# 1-Schematic_STM32_CC1101_USBMALE_PCBANTE.net
KiCad netlist of a schematic drawn in EasyEDA
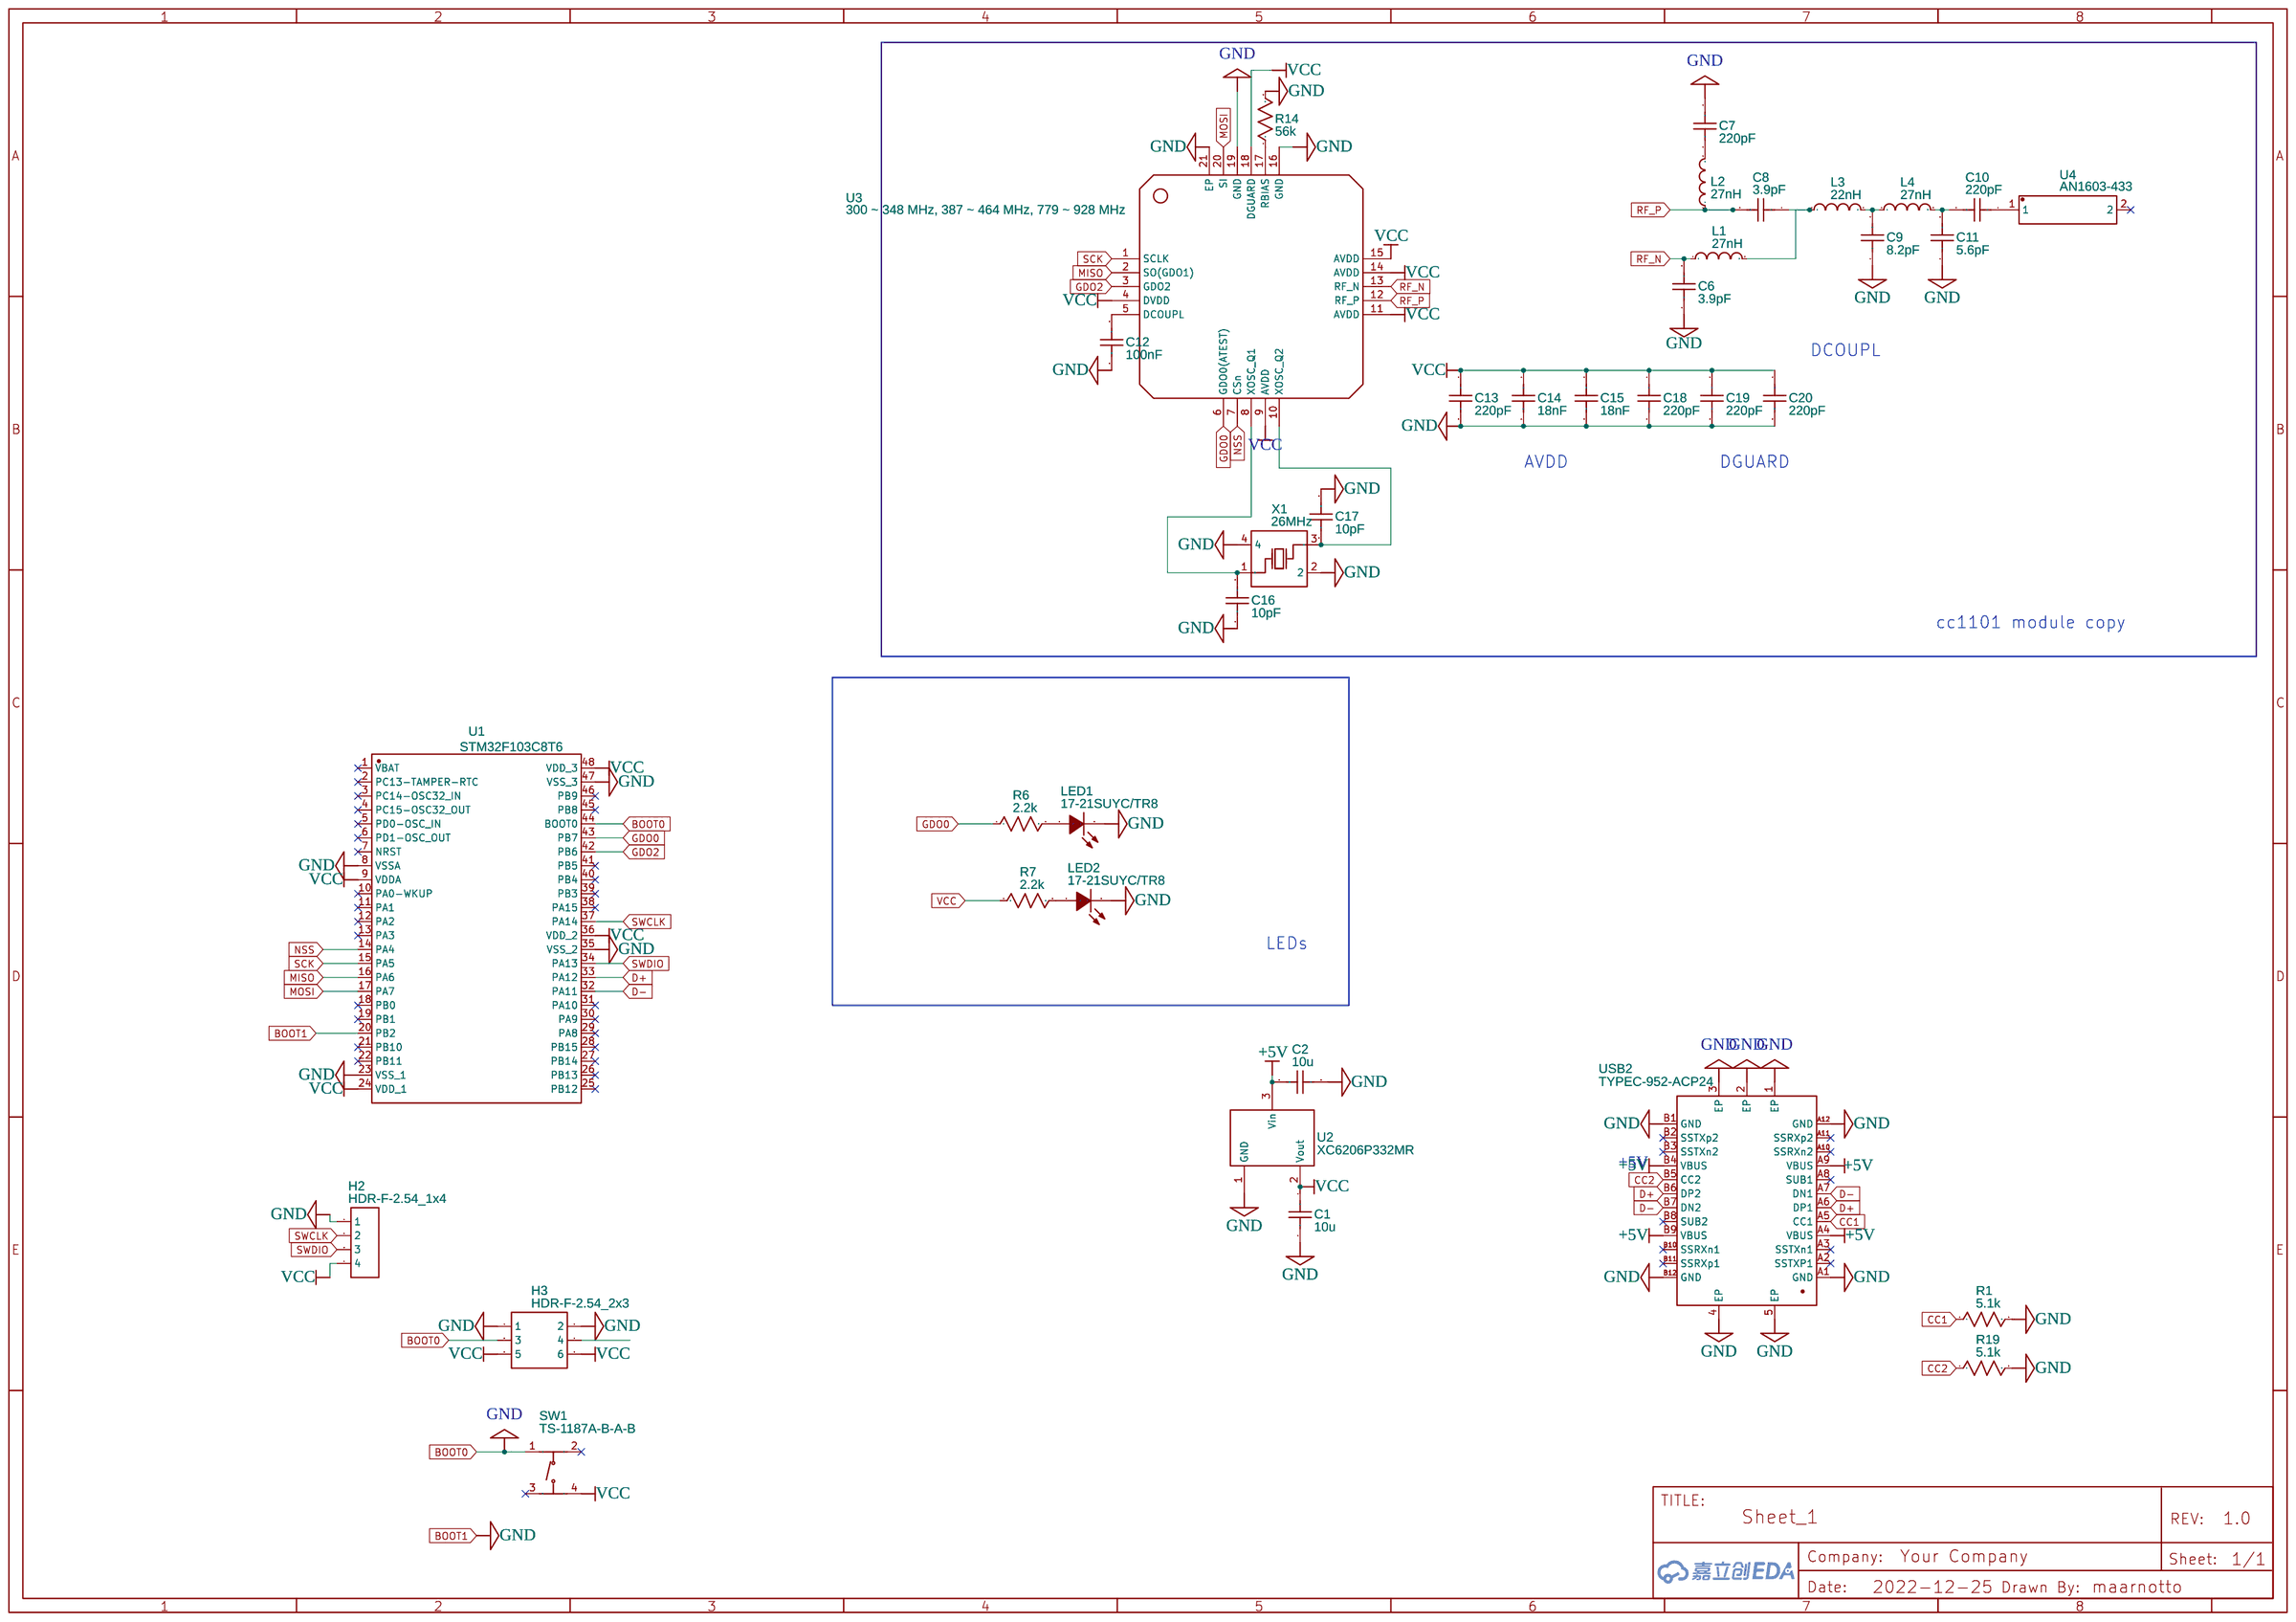
[diagram p0: schematic sheet]

(export (version "E")
  (design (tool "Eeschema 10.0.6"))
  (components
    (comp (ref "C1") (value "10u") (libsource (lib "") (part "C_0603_US_1")))
    (comp (ref "C2") (value "10u") (libsource (lib "") (part "C_0603_US")))
    (comp (ref "C6") (value "3.9pF") (libsource (lib "") (part "C_0402_US_2")))
    (comp (ref "C7") (value "220pF") (libsource (lib "") (part "C_0402_US_2")))
    (comp (ref "C8") (value "3.9pF") (libsource (lib "") (part "C_0402_US")))
    (comp (ref "C9") (value "8.2pF") (libsource (lib "") (part "C_0402_US_2")))
    (comp (ref "C10") (value "220pF") (libsource (lib "") (part "C_0402_US")))
    (comp (ref "C11") (value "5.6pF") (libsource (lib "") (part "C_0402_US_2")))
    (comp (ref "C12") (value "100nF") (libsource (lib "") (part "C_0402_US_1")))
    (comp (ref "C13") (value "220pF") (libsource (lib "") (part "C_0402_US_1")))
    (comp (ref "C14") (value "18nF") (libsource (lib "") (part "C_0402_US_1")))
    (comp (ref "C15") (value "18nF") (libsource (lib "") (part "C_0402_US_1")))
    (comp (ref "C16") (value "10pF") (libsource (lib "") (part "C_0402_US_1")))
    (comp (ref "C17") (value "10pF") (libsource (lib "") (part "C_0402_US_2")))
    (comp (ref "C18") (value "220pF") (libsource (lib "") (part "C_0402_US_1")))
    (comp (ref "C19") (value "220pF") (libsource (lib "") (part "C_0402_US_1")))
    (comp (ref "C20") (value "220pF") (libsource (lib "") (part "C_0402_US_1")))
    (comp (ref "H2")
      (value "HDR-F-2.54_1x4")
      (fields (field (name "BOM_Supplier Part") "C225501"))
      (libsource (lib "") (part "HDR-F-2.54_1x4"))
    )
    (comp (ref "H3")
      (value "HDR-F-2.54_2x3")
      (fields (field (name "BOM_Supplier Part") "C65114"))
      (libsource (lib "") (part "HDR-F-2.54_2x3"))
    )
    (comp (ref "L1") (value "27nH") (libsource (lib "") (part "L0402_US")))
    (comp (ref "L2") (value "27nH") (libsource (lib "") (part "L0402_US_1")))
    (comp (ref "L3") (value "22nH") (libsource (lib "") (part "L0402_US")))
    (comp (ref "L4") (value "27nH") (libsource (lib "") (part "L0402_US")))
    (comp (ref "LED1")
      (value "17-21SUYC/TR8")
      (fields
        (field (name "BOM_Manufacturer Part") "KT-0805黄灯 (SMT业务专用)")
        (field (name "BOM_Supplier Part") "C2296")
      )
      (libsource (lib "") (part "17-21SUYC/TR8"))
    )
    (comp (ref "LED2")
      (value "17-21SUYC/TR8")
      (fields
        (field (name "BOM_Manufacturer Part") "KT-0805黄灯 (SMT业务专用)")
        (field (name "BOM_Supplier Part") "C2296")
      )
      (libsource (lib "") (part "17-21SUYC/TR8"))
    )
    (comp (ref "R1") (value "5.1k") (libsource (lib "") (part "R_0603_US")))
    (comp (ref "R6") (value "2.2k") (libsource (lib "") (part "R_0603_US")))
    (comp (ref "R7") (value "2.2k") (libsource (lib "") (part "R_0603_US")))
    (comp (ref "R14") (value "56k") (libsource (lib "") (part "R_0402_US")))
    (comp (ref "R19") (value "5.1k") (libsource (lib "") (part "R_0603_US")))
    (comp (ref "SW1")
      (value "TS-1187A-B-A-B")
      (fields (field (name "BOM_Supplier Part") "C318884"))
      (libsource (lib "") (part "TS-1187A-B-A-B"))
    )
    (comp (ref "U1")
      (value "STM32F103C8T6")
      (fields (field (name "BOM_Supplier Part") "C8734"))
      (libsource (lib "") (part "STM32F103C8T6"))
    )
    (comp (ref "U2")
      (value "XC6206P332MR")
      (fields (field (name "BOM_Supplier Part") "C5446"))
      (libsource (lib "") (part "XC6206P332MR"))
    )
    (comp (ref "U3")
      (value "300 ~ 348 MHz, 387 ~ 464 MHz, 779 ~ 928 MHz")
      (fields (field (name "BOM_Manufacturer Part") "CC1101RGPR") (field (name "BOM_Supplier Part") "C29953"))
      (libsource (lib "") (part "CC1101RGPR"))
    )
    (comp (ref "U4")
      (value "AN1603-433")
      (fields (field (name "BOM_Supplier Part") "C122806"))
      (libsource (lib "") (part "AN1603-433"))
    )
    (comp (ref "USB2")
      (value "TYPEC-952-ACP24")
      (fields (field (name "BOM_Supplier Part") "C2840398"))
      (libsource (lib "") (part "TYPEC-952-ACP24"))
    )
    (comp (ref "X1")
      (value "26MHz")
      (fields
        (field (name "BOM_Manufacturer Part") "3S26000333")
        (field (name "BOM_Supplier Part") "C431163")
      )
      (libsource (lib "") (part "3S26000333"))
    )
  )
  (nets
    (net (code "1") (name "+5V") (class "Default")
      (node (ref "C2") (pin "2") (pinfunction "2_2") (pintype "unspecified"))
      (node (ref "U2") (pin "3") (pinfunction "Vin_3") (pintype "unspecified"))
      (node (ref "USB2") (pin "A4") (pinfunction "VBUS_A4") (pintype "unspecified"))
      (node (ref "USB2") (pin "A9") (pinfunction "VBUS_A9") (pintype "unspecified"))
      (node (ref "USB2") (pin "B4") (pinfunction "VBUS_B4") (pintype "unspecified"))
      (node (ref "USB2") (pin "B9") (pinfunction "VBUS_B9") (pintype "unspecified"))
    )
    (net (code "2") (name "BOOT0") (class "Default")
      (node (ref "C1") (pin "2") (pinfunction "2_2") (pintype "unspecified"))
      (node (ref "C11") (pin "1") (pinfunction "1_1") (pintype "unspecified"))
      (node (ref "C12") (pin "2") (pinfunction "2_2") (pintype "unspecified"))
      (node (ref "C13") (pin "2") (pinfunction "2_2") (pintype "unspecified"))
      (node (ref "C14") (pin "2") (pinfunction "2_2") (pintype "unspecified"))
      (node (ref "C15") (pin "2") (pinfunction "2_2") (pintype "unspecified"))
      (node (ref "C16") (pin "2") (pinfunction "2_2") (pintype "unspecified"))
      (node (ref "C17") (pin "2") (pinfunction "2_2") (pintype "unspecified"))
      (node (ref "C18") (pin "2") (pinfunction "2_2") (pintype "unspecified"))
      (node (ref "C19") (pin "2") (pinfunction "2_2") (pintype "unspecified"))
      (node (ref "C2") (pin "1") (pinfunction "1_1") (pintype "unspecified"))
      (node (ref "C20") (pin "2") (pinfunction "2_2") (pintype "unspecified"))
      (node (ref "C6") (pin "1") (pinfunction "1_1") (pintype "unspecified"))
      (node (ref "C7") (pin "2") (pinfunction "2_2") (pintype "unspecified"))
      (node (ref "C9") (pin "1") (pinfunction "1_1") (pintype "unspecified"))
      (node (ref "H2") (pin "1") (pinfunction "1_1") (pintype "unspecified"))
      (node (ref "H3") (pin "1") (pinfunction "1_1") (pintype "input"))
      (node (ref "H3") (pin "2") (pinfunction "2_2") (pintype "input"))
      (node (ref "H3") (pin "3") (pinfunction "3_3") (pintype "input"))
      (node (ref "LED1") (pin "2") (pinfunction "-_2") (pintype "unspecified"))
      (node (ref "LED2") (pin "2") (pinfunction "-_2") (pintype "unspecified"))
      (node (ref "R1") (pin "2") (pinfunction "2_2") (pintype "unspecified"))
      (node (ref "R14") (pin "2") (pinfunction "2_2") (pintype "unspecified"))
      (node (ref "R19") (pin "2") (pinfunction "2_2") (pintype "unspecified"))
      (node (ref "SW1") (pin "1") (pinfunction "A_1") (pintype "unspecified"))
      (node (ref "U1") (pin "20") (pinfunction "PB2_20") (pintype "unspecified"))
      (node (ref "U1") (pin "23") (pinfunction "VSS_1_23") (pintype "unspecified"))
      (node (ref "U1") (pin "35") (pinfunction "VSS_2_35") (pintype "unspecified"))
      (node (ref "U1") (pin "44") (pinfunction "BOOT0_44") (pintype "unspecified"))
      (node (ref "U1") (pin "47") (pinfunction "VSS_3_47") (pintype "unspecified"))
      (node (ref "U1") (pin "8") (pinfunction "VSSA_8") (pintype "unspecified"))
      (node (ref "U2") (pin "1") (pinfunction "GND_1") (pintype "unspecified"))
      (node (ref "U3") (pin "16") (pinfunction "GND_16") (pintype "unspecified"))
      (node (ref "U3") (pin "19") (pinfunction "GND_19") (pintype "unspecified"))
      (node (ref "U3") (pin "21") (pinfunction "EP_21") (pintype "unspecified"))
      (node (ref "USB2") (pin "1") (pinfunction "EP_1") (pintype "unspecified"))
      (node (ref "USB2") (pin "2") (pinfunction "EP_2") (pintype "unspecified"))
      (node (ref "USB2") (pin "3") (pinfunction "EP_3") (pintype "unspecified"))
      (node (ref "USB2") (pin "4") (pinfunction "EP_4") (pintype "unspecified"))
      (node (ref "USB2") (pin "5") (pinfunction "EP_5") (pintype "unspecified"))
      (node (ref "USB2") (pin "A1") (pinfunction "GND_A1") (pintype "unspecified"))
      (node (ref "USB2") (pin "A12") (pinfunction "GND_A12") (pintype "unspecified"))
      (node (ref "USB2") (pin "B1") (pinfunction "GND_B1") (pintype "unspecified"))
      (node (ref "USB2") (pin "B12") (pinfunction "GND_B12") (pintype "unspecified"))
      (node (ref "X1") (pin "2") (pinfunction "2_2") (pintype "unspecified"))
      (node (ref "X1") (pin "4") (pinfunction "4_4") (pintype "unspecified"))
    )
    (net (code "3") (name "CC1") (class "Default")
      (node (ref "R1") (pin "1") (pinfunction "1_1") (pintype "unspecified"))
      (node (ref "USB2") (pin "A5") (pinfunction "CC1_A5") (pintype "unspecified"))
    )
    (net (code "4") (name "CC2") (class "Default")
      (node (ref "R19") (pin "1") (pinfunction "1_1") (pintype "unspecified"))
      (node (ref "USB2") (pin "B5") (pinfunction "CC2_B5") (pintype "unspecified"))
    )
    (net (code "5") (name "D+") (class "Default")
      (node (ref "U1") (pin "33") (pinfunction "PA12_33") (pintype "unspecified"))
      (node (ref "USB2") (pin "A6") (pinfunction "DP1_A6") (pintype "unspecified"))
      (node (ref "USB2") (pin "B6") (pinfunction "DP2_B6") (pintype "unspecified"))
    )
    (net (code "6") (name "D-") (class "Default")
      (node (ref "U1") (pin "32") (pinfunction "PA11_32") (pintype "unspecified"))
      (node (ref "USB2") (pin "A7") (pinfunction "DN1_A7") (pintype "unspecified"))
      (node (ref "USB2") (pin "B7") (pinfunction "DN2_B7") (pintype "unspecified"))
    )
    (net (code "7") (name "GDO0") (class "Default")
      (node (ref "R6") (pin "1") (pinfunction "1_1") (pintype "unspecified"))
      (node (ref "U1") (pin "43") (pinfunction "PB7_43") (pintype "unspecified"))
      (node (ref "U3") (pin "6") (pinfunction "GDO0(ATEST)_6") (pintype "unspecified"))
    )
    (net (code "8") (name "GDO2") (class "Default")
      (node (ref "U1") (pin "42") (pinfunction "PB6_42") (pintype "unspecified"))
      (node (ref "U3") (pin "3") (pinfunction "GDO2_3") (pintype "unspecified"))
    )
    (net (code "9") (name "MISO") (class "Default")
      (node (ref "U1") (pin "16") (pinfunction "PA6_16") (pintype "unspecified"))
      (node (ref "U3") (pin "2") (pinfunction "SO(GDO1)_2") (pintype "unspecified"))
    )
    (net (code "10") (name "MOSI") (class "Default")
      (node (ref "U1") (pin "17") (pinfunction "PA7_17") (pintype "unspecified"))
      (node (ref "U3") (pin "20") (pinfunction "SI_20") (pintype "unspecified"))
    )
    (net (code "11") (name "NSS") (class "Default")
      (node (ref "U1") (pin "14") (pinfunction "PA4_14") (pintype "unspecified"))
      (node (ref "U3") (pin "7") (pinfunction "CSn_7") (pintype "unspecified"))
    )
    (net (code "12") (name "Net-(C7-Pad1)") (class "Default")
      (node (ref "C7") (pin "1") (pinfunction "1_1") (pintype "unspecified"))
      (node (ref "L2") (pin "2") (pinfunction "2_2") (pintype "unspecified"))
    )
    (net (code "13") (name "Net-(C8-Pad1)") (class "Default")
      (node (ref "C8") (pin "1") (pinfunction "1_1") (pintype "unspecified"))
      (node (ref "L1") (pin "2") (pinfunction "2_2") (pintype "unspecified"))
      (node (ref "L3") (pin "1") (pinfunction "1_1") (pintype "unspecified"))
    )
    (net (code "14") (name "Net-(C9-Pad2)") (class "Default")
      (node (ref "C9") (pin "2") (pinfunction "2_2") (pintype "unspecified"))
      (node (ref "L3") (pin "2") (pinfunction "2_2") (pintype "unspecified"))
      (node (ref "L4") (pin "1") (pinfunction "1_1") (pintype "unspecified"))
    )
    (net (code "15") (name "Net-(C10-Pad1)") (class "Default")
      (node (ref "C10") (pin "1") (pinfunction "1_1") (pintype "unspecified"))
      (node (ref "U4") (pin "1") (pinfunction "1_1") (pintype "unspecified"))
    )
    (net (code "16") (name "Net-(C10-Pad2)") (class "Default")
      (node (ref "C10") (pin "2") (pinfunction "2_2") (pintype "unspecified"))
      (node (ref "C11") (pin "2") (pinfunction "2_2") (pintype "unspecified"))
      (node (ref "L4") (pin "2") (pinfunction "2_2") (pintype "unspecified"))
    )
    (net (code "17") (name "Net-(LED1-+)") (class "Default")
      (node (ref "LED1") (pin "1") (pinfunction "+_1") (pintype "unspecified"))
      (node (ref "R6") (pin "2") (pinfunction "2_2") (pintype "unspecified"))
    )
    (net (code "18") (name "Net-(LED2-+)") (class "Default")
      (node (ref "LED2") (pin "1") (pinfunction "+_1") (pintype "unspecified"))
      (node (ref "R7") (pin "2") (pinfunction "2_2") (pintype "unspecified"))
    )
    (net (code "19") (name "Net-(U3-DCOUPL)") (class "Default")
      (node (ref "C12") (pin "1") (pinfunction "1_1") (pintype "unspecified"))
      (node (ref "U3") (pin "5") (pinfunction "DCOUPL_5") (pintype "unspecified"))
    )
    (net (code "20") (name "Net-(U3-RBIAS)") (class "Default")
      (node (ref "R14") (pin "1") (pinfunction "1_1") (pintype "unspecified"))
      (node (ref "U3") (pin "17") (pinfunction "RBIAS_17") (pintype "unspecified"))
    )
    (net (code "21") (name "Net-(U3-XOSC_Q1)") (class "Default")
      (node (ref "C16") (pin "1") (pinfunction "1_1") (pintype "unspecified"))
      (node (ref "U3") (pin "8") (pinfunction "XOSC_Q1_8") (pintype "unspecified"))
      (node (ref "X1") (pin "1") (pinfunction "OSC1_1") (pintype "unspecified"))
    )
    (net (code "22") (name "Net-(U3-XOSC_Q2)") (class "Default")
      (node (ref "C17") (pin "1") (pinfunction "1_1") (pintype "unspecified"))
      (node (ref "U3") (pin "10") (pinfunction "XOSC_Q2_10") (pintype "unspecified"))
      (node (ref "X1") (pin "3") (pinfunction "OSC2_3") (pintype "unspecified"))
    )
    (net (code "23") (name "RF_N") (class "Default")
      (node (ref "C6") (pin "2") (pinfunction "2_2") (pintype "unspecified"))
      (node (ref "L1") (pin "1") (pinfunction "1_1") (pintype "unspecified"))
      (node (ref "U3") (pin "13") (pinfunction "RF_N_13") (pintype "unspecified"))
    )
    (net (code "24") (name "RF_P") (class "Default")
      (node (ref "C8") (pin "2") (pinfunction "2_2") (pintype "unspecified"))
      (node (ref "L2") (pin "1") (pinfunction "1_1") (pintype "unspecified"))
      (node (ref "U3") (pin "12") (pinfunction "RF_P_12") (pintype "unspecified"))
    )
    (net (code "25") (name "SCK") (class "Default")
      (node (ref "U1") (pin "15") (pinfunction "PA5_15") (pintype "unspecified"))
      (node (ref "U3") (pin "1") (pinfunction "SCLK_1") (pintype "unspecified"))
    )
    (net (code "26") (name "SWCLK") (class "Default")
      (node (ref "H2") (pin "2") (pinfunction "2_2") (pintype "unspecified"))
      (node (ref "U1") (pin "37") (pinfunction "PA14_37") (pintype "unspecified"))
    )
    (net (code "27") (name "SWDIO") (class "Default")
      (node (ref "H2") (pin "3") (pinfunction "3_3") (pintype "unspecified"))
      (node (ref "U1") (pin "34") (pinfunction "PA13_34") (pintype "unspecified"))
    )
    (net (code "28") (name "VCC") (class "Default")
      (node (ref "C1") (pin "1") (pinfunction "1_1") (pintype "unspecified"))
      (node (ref "C13") (pin "1") (pinfunction "1_1") (pintype "unspecified"))
      (node (ref "C14") (pin "1") (pinfunction "1_1") (pintype "unspecified"))
      (node (ref "C15") (pin "1") (pinfunction "1_1") (pintype "unspecified"))
      (node (ref "C18") (pin "1") (pinfunction "1_1") (pintype "unspecified"))
      (node (ref "C19") (pin "1") (pinfunction "1_1") (pintype "unspecified"))
      (node (ref "C20") (pin "1") (pinfunction "1_1") (pintype "unspecified"))
      (node (ref "H2") (pin "4") (pinfunction "4_4") (pintype "unspecified"))
      (node (ref "H3") (pin "5") (pinfunction "5_5") (pintype "input"))
      (node (ref "H3") (pin "6") (pinfunction "6_6") (pintype "input"))
      (node (ref "R7") (pin "1") (pinfunction "1_1") (pintype "unspecified"))
      (node (ref "SW1") (pin "4") (pinfunction "D_4") (pintype "unspecified"))
      (node (ref "U1") (pin "24") (pinfunction "VDD_1_24") (pintype "unspecified"))
      (node (ref "U1") (pin "36") (pinfunction "VDD_2_36") (pintype "unspecified"))
      (node (ref "U1") (pin "48") (pinfunction "VDD_3_48") (pintype "unspecified"))
      (node (ref "U1") (pin "9") (pinfunction "VDDA_9") (pintype "unspecified"))
      (node (ref "U2") (pin "2") (pinfunction "Vout_2") (pintype "unspecified"))
      (node (ref "U3") (pin "11") (pinfunction "AVDD_11") (pintype "unspecified"))
      (node (ref "U3") (pin "14") (pinfunction "AVDD_14") (pintype "unspecified"))
      (node (ref "U3") (pin "15") (pinfunction "AVDD_15") (pintype "unspecified"))
      (node (ref "U3") (pin "18") (pinfunction "DGUARD_18") (pintype "unspecified"))
      (node (ref "U3") (pin "4") (pinfunction "DVDD_4") (pintype "unspecified"))
      (node (ref "U3") (pin "9") (pinfunction "AVDD_9") (pintype "unspecified"))
    )
    (net (code "29") (name "unconnected-(H3-Pad4)") (class "Default")
      (node (ref "H3") (pin "4") (pinfunction "4_4") (pintype "input"))
    )
    (net (code "30") (name "unconnected-(SW1-B-Pad2)") (class "Default")
      (node (ref "SW1") (pin "2") (pinfunction "B_2") (pintype "unspecified+no_connect"))
    )
    (net (code "31") (name "unconnected-(SW1-C-Pad3)") (class "Default")
      (node (ref "SW1") (pin "3") (pinfunction "C_3") (pintype "unspecified+no_connect"))
    )
    (net (code "32") (name "unconnected-(U1-NRST-Pad7)") (class "Default")
      (node (ref "U1") (pin "7") (pinfunction "NRST_7") (pintype "unspecified+no_connect"))
    )
    (net (code "33") (name "unconnected-(U1-PA0-WKUP-Pad10)") (class "Default")
      (node (ref "U1") (pin "10") (pinfunction "PA0-WKUP_10") (pintype "unspecified+no_connect"))
    )
    (net (code "34") (name "unconnected-(U1-PA1-Pad11)") (class "Default")
      (node (ref "U1") (pin "11") (pinfunction "PA1_11") (pintype "unspecified+no_connect"))
    )
    (net (code "35") (name "unconnected-(U1-PA2-Pad12)") (class "Default")
      (node (ref "U1") (pin "12") (pinfunction "PA2_12") (pintype "unspecified+no_connect"))
    )
    (net (code "36") (name "unconnected-(U1-PA3-Pad13)") (class "Default")
      (node (ref "U1") (pin "13") (pinfunction "PA3_13") (pintype "unspecified+no_connect"))
    )
    (net (code "37") (name "unconnected-(U1-PA8-Pad29)") (class "Default")
      (node (ref "U1") (pin "29") (pinfunction "PA8_29") (pintype "unspecified+no_connect"))
    )
    (net (code "38") (name "unconnected-(U1-PA9-Pad30)") (class "Default")
      (node (ref "U1") (pin "30") (pinfunction "PA9_30") (pintype "unspecified+no_connect"))
    )
    (net (code "39") (name "unconnected-(U1-PA10-Pad31)") (class "Default")
      (node (ref "U1") (pin "31") (pinfunction "PA10_31") (pintype "unspecified+no_connect"))
    )
    (net (code "40") (name "unconnected-(U1-PA15-Pad38)") (class "Default")
      (node (ref "U1") (pin "38") (pinfunction "PA15_38") (pintype "unspecified+no_connect"))
    )
    (net (code "41") (name "unconnected-(U1-PB0-Pad18)") (class "Default")
      (node (ref "U1") (pin "18") (pinfunction "PB0_18") (pintype "unspecified+no_connect"))
    )
    (net (code "42") (name "unconnected-(U1-PB1-Pad19)") (class "Default")
      (node (ref "U1") (pin "19") (pinfunction "PB1_19") (pintype "unspecified+no_connect"))
    )
    (net (code "43") (name "unconnected-(U1-PB3-Pad39)") (class "Default")
      (node (ref "U1") (pin "39") (pinfunction "PB3_39") (pintype "unspecified+no_connect"))
    )
    (net (code "44") (name "unconnected-(U1-PB4-Pad40)") (class "Default")
      (node (ref "U1") (pin "40") (pinfunction "PB4_40") (pintype "unspecified+no_connect"))
    )
    (net (code "45") (name "unconnected-(U1-PB5-Pad41)") (class "Default")
      (node (ref "U1") (pin "41") (pinfunction "PB5_41") (pintype "unspecified+no_connect"))
    )
    (net (code "46") (name "unconnected-(U1-PB8-Pad45)") (class "Default")
      (node (ref "U1") (pin "45") (pinfunction "PB8_45") (pintype "unspecified+no_connect"))
    )
    (net (code "47") (name "unconnected-(U1-PB9-Pad46)") (class "Default")
      (node (ref "U1") (pin "46") (pinfunction "PB9_46") (pintype "unspecified+no_connect"))
    )
    (net (code "48") (name "unconnected-(U1-PB10-Pad21)") (class "Default")
      (node (ref "U1") (pin "21") (pinfunction "PB10_21") (pintype "unspecified+no_connect"))
    )
    (net (code "49") (name "unconnected-(U1-PB11-Pad22)") (class "Default")
      (node (ref "U1") (pin "22") (pinfunction "PB11_22") (pintype "unspecified+no_connect"))
    )
    (net (code "50") (name "unconnected-(U1-PB12-Pad25)") (class "Default")
      (node (ref "U1") (pin "25") (pinfunction "PB12_25") (pintype "unspecified+no_connect"))
    )
    (net (code "51") (name "unconnected-(U1-PB13-Pad26)") (class "Default")
      (node (ref "U1") (pin "26") (pinfunction "PB13_26") (pintype "unspecified+no_connect"))
    )
    (net (code "52") (name "unconnected-(U1-PB14-Pad27)") (class "Default")
      (node (ref "U1") (pin "27") (pinfunction "PB14_27") (pintype "unspecified+no_connect"))
    )
    (net (code "53") (name "unconnected-(U1-PB15-Pad28)") (class "Default")
      (node (ref "U1") (pin "28") (pinfunction "PB15_28") (pintype "unspecified+no_connect"))
    )
    (net (code "54") (name "unconnected-(U1-PC13-TAMPER-RTC-Pad2)") (class "Default")
      (node (ref "U1") (pin "2") (pinfunction "PC13-TAMPER-RTC_2") (pintype "unspecified+no_connect"))
    )
    (net (code "55") (name "unconnected-(U1-PC14-OSC32_IN-Pad3)") (class "Default")
      (node (ref "U1") (pin "3") (pinfunction "PC14-OSC32_IN_3") (pintype "unspecified+no_connect"))
    )
    (net (code "56") (name "unconnected-(U1-PC15-OSC32_OUT-Pad4)") (class "Default")
      (node (ref "U1") (pin "4") (pinfunction "PC15-OSC32_OUT_4") (pintype "unspecified+no_connect"))
    )
    (net (code "57") (name "unconnected-(U1-PD0-OSC_IN-Pad5)") (class "Default")
      (node (ref "U1") (pin "5") (pinfunction "PD0-OSC_IN_5") (pintype "unspecified+no_connect"))
    )
    (net (code "58") (name "unconnected-(U1-PD1-OSC_OUT-Pad6)") (class "Default")
      (node (ref "U1") (pin "6") (pinfunction "PD1-OSC_OUT_6") (pintype "unspecified+no_connect"))
    )
    (net (code "59") (name "unconnected-(U1-VBAT-Pad1)") (class "Default")
      (node (ref "U1") (pin "1") (pinfunction "VBAT_1") (pintype "unspecified+no_connect"))
    )
    (net (code "60") (name "unconnected-(U4-Pad2)") (class "Default")
      (node (ref "U4") (pin "2") (pinfunction "2_2") (pintype "unspecified+no_connect"))
    )
    (net (code "61") (name "unconnected-(USB2-SSRXn1-PadB10)") (class "Default")
      (node (ref "USB2") (pin "B10") (pinfunction "SSRXn1_B10") (pintype "unspecified+no_connect"))
    )
    (net (code "62") (name "unconnected-(USB2-SSRXn2-PadA10)") (class "Default")
      (node (ref "USB2") (pin "A10") (pinfunction "SSRXn2_A10") (pintype "unspecified+no_connect"))
    )
    (net (code "63") (name "unconnected-(USB2-SSRXp1-PadB11)") (class "Default")
      (node (ref "USB2") (pin "B11") (pinfunction "SSRXp1_B11") (pintype "unspecified+no_connect"))
    )
    (net (code "64") (name "unconnected-(USB2-SSRXp2-PadA11)") (class "Default")
      (node (ref "USB2") (pin "A11") (pinfunction "SSRXp2_A11") (pintype "unspecified+no_connect"))
    )
    (net (code "65") (name "unconnected-(USB2-SSTXP1-PadA2)") (class "Default")
      (node (ref "USB2") (pin "A2") (pinfunction "SSTXP1_A2") (pintype "unspecified+no_connect"))
    )
    (net (code "66") (name "unconnected-(USB2-SSTXn1-PadA3)") (class "Default")
      (node (ref "USB2") (pin "A3") (pinfunction "SSTXn1_A3") (pintype "unspecified+no_connect"))
    )
    (net (code "67") (name "unconnected-(USB2-SSTXn2-PadB3)") (class "Default")
      (node (ref "USB2") (pin "B3") (pinfunction "SSTXn2_B3") (pintype "unspecified+no_connect"))
    )
    (net (code "68") (name "unconnected-(USB2-SSTXp2-PadB2)") (class "Default")
      (node (ref "USB2") (pin "B2") (pinfunction "SSTXp2_B2") (pintype "unspecified+no_connect"))
    )
    (net (code "69") (name "unconnected-(USB2-SUB1-PadA8)") (class "Default")
      (node (ref "USB2") (pin "A8") (pinfunction "SUB1_A8") (pintype "unspecified+no_connect"))
    )
    (net (code "70") (name "unconnected-(USB2-SUB2-PadB8)") (class "Default")
      (node (ref "USB2") (pin "B8") (pinfunction "SUB2_B8") (pintype "unspecified+no_connect"))
    )
  )
)
